# power.net
KiCad netlist of a schematic drawn in Altium Designer
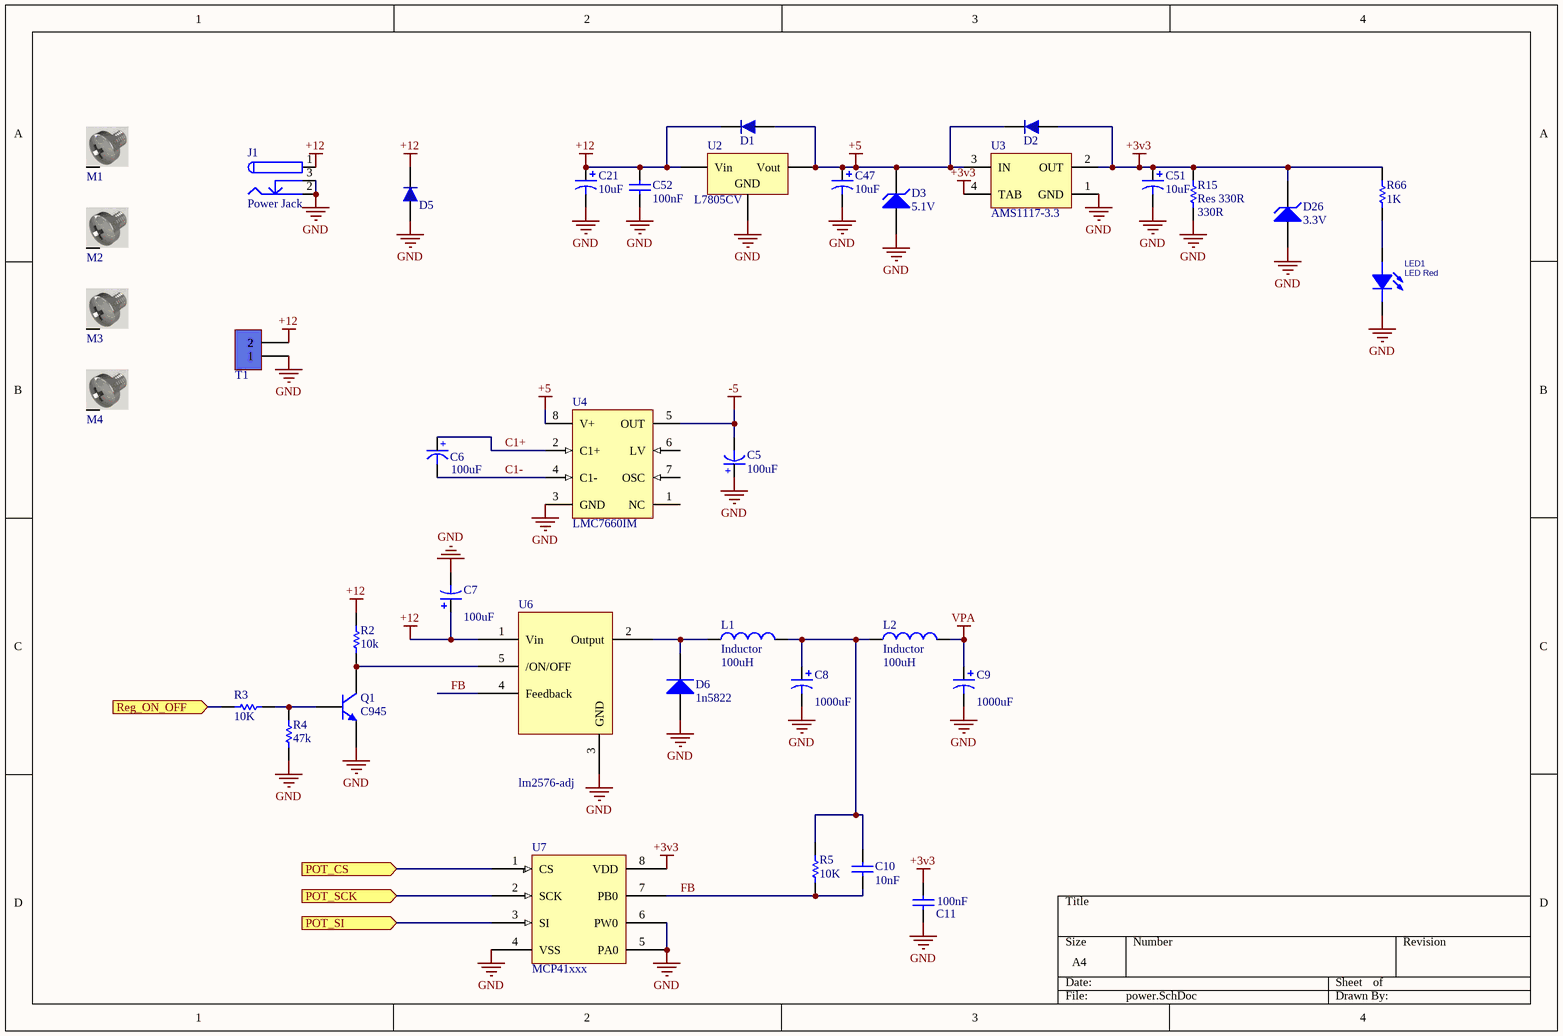
[diagram p0: power.SchDoc]

(export (version "E")
  (design (tool "Eeschema 10.0.6"))
  (components
    (comp (ref "C5")
      (value "100uF")
      (footprint "Cap SMD electrolite-6.3mm")
      (description "Polar Capacitor")
      (fields (field (name "VOLTAGE") "16V") (field (name "DESIGNER") "Saeid Jorablo"))
      (libsource (lib "Altium") (part "Cap-Polar"))
    )
    (comp (ref "C6")
      (value "100uF")
      (footprint "Cap SMD electrolite-6.3mm")
      (description "Polar Capacitor")
      (fields (field (name "VOLTAGE") "16V") (field (name "DESIGNER") "Saeid Jorablo"))
      (libsource (lib "Altium") (part "Cap-Polar"))
    )
    (comp (ref "C7")
      (value "100uF")
      (footprint "Cap SMD electrolite-6.3mm")
      (description "Polarized Capacitor (Radial)")
      (fields (field (name "PUBLISHER") "Altium Limited"))
      (libsource (lib "Miscellaneous Devices") (part "Cap Pol1"))
    )
    (comp (ref "C8")
      (value "1000uF")
      (footprint "PcbLib1:Cap SMD electrolite-10.3mm")
      (description "Polarized Capacitor (Radial)")
      (fields (field (name "PUBLISHER") "Altium Limited"))
      (libsource (lib "Miscellaneous Devices") (part "Cap Pol1"))
    )
    (comp (ref "C9")
      (value "1000uF")
      (footprint "PcbLib1:Cap SMD electrolite-10.3mm")
      (description "Polarized Capacitor (Radial)")
      (fields (field (name "PUBLISHER") "Altium Limited"))
      (libsource (lib "Miscellaneous Devices") (part "Cap Pol1"))
    )
    (comp (ref "C10")
      (value "10nF")
      (footprint "SMD_CAP_0805")
      (description "CAP-100Nf")
      (libsource (lib "Altium library (www.AVRelec.com)") (part "Cap ceramic"))
    )
    (comp (ref "C11")
      (value "100nF")
      (footprint "SMD_CAP_0805")
      (description "CAP-100Nf")
      (libsource (lib "Altium library (www.AVRelec.com)") (part "Cap ceramic"))
    )
    (comp (ref "C21")
      (value "10uF")
      (footprint "CAP0805")
      (description "CAP seramic")
      (fields (field (name "Comment") "cap 10uF") (field (name "PUBLISHER") "Altium Limited"))
      (libsource (lib "Miscellaneous Devices") (part "Cap Pol1"))
    )
    (comp (ref "C47")
      (value "10uF")
      (footprint "CAP0805")
      (description "CAP seramic")
      (fields (field (name "Comment") "cap 10uF") (field (name "PUBLISHER") "Altium Limited"))
      (libsource (lib "Miscellaneous Devices") (part "Cap Pol1"))
    )
    (comp (ref "C51")
      (value "10uF")
      (footprint "CAP0805")
      (description "CAP seramic")
      (fields (field (name "Comment") "cap 10uF") (field (name "PUBLISHER") "Altium Limited"))
      (libsource (lib "Miscellaneous Devices") (part "Cap Pol1"))
    )
    (comp (ref "C52")
      (value "100nF")
      (footprint "CAP0805")
      (description "CAP seramic")
      (fields (field (name "Comment") "cap 100nF"))
      (libsource (lib "Altium library (www.AVRelec.com)") (part "Cap ceramic"))
    )
    (comp (ref "D1")
      (value "uf4007")
      (footprint "DIOM4629X24N")
      (description "Standard Rectifiers")
      (fields (field (name "MANUFACTURER") "DC COMPONENTS") (field (name "DESIGNER") "Abbas Basereh"))
      (libsource (lib "Altium (2)") (part "1n4007 SMD M7"))
    )
    (comp (ref "D2")
      (value "uf4007")
      (footprint "DIOM4629X24N")
      (description "Standard Rectifiers")
      (fields (field (name "MANUFACTURER") "DC COMPONENTS") (field (name "DESIGNER") "Abbas Basereh"))
      (libsource (lib "Altium (2)") (part "1n4007 SMD M7"))
    )
    (comp (ref "D3")
      (value "5.1V")
      (footprint "Diode 1n4148 SMD")
      (description "Zener Diode")
      (fields (field (name "PUBLISHER") "Altium Limited"))
      (libsource (lib "Miscellaneous Devices") (part "D Zener"))
    )
    (comp (ref "D5")
      (value "uf4007")
      (footprint "DIOM4629X24N")
      (description "Standard Rectifiers")
      (fields (field (name "MANUFACTURER") "DC COMPONENTS") (field (name "DESIGNER") "Abbas Basereh"))
      (libsource (lib "Altium (2)") (part "1n4007 SMD M7"))
    )
    (comp (ref "D6")
      (value "1n5822")
      (footprint "DO214AC SMA")
      (description "1 Amp General Purpose Rectifier")
      (fields (field (name "PUBLISHER") "Altium Limited"))
      (libsource (lib "Miscellaneous Devices") (part "Diode 1N4007"))
    )
    (comp (ref "D26")
      (value "3.3V")
      (footprint "Diode 1n4148 SMD")
      (description "Zener Diode")
      (fields (field (name "PUBLISHER") "Altium Limited"))
      (libsource (lib "Miscellaneous Devices") (part "D Zener"))
    )
    (comp (ref "J1")
      (value "Power Jack")
      (footprint "Power Jack")
      (fields (field (name "DESIGNER") "Saeid Jorablo"))
      (libsource (lib "My Library") (part "Power Jack"))
    )
    (comp (ref "L1")
      (value "Inductor")
      (footprint "inductor")
      (description "SMD Inductor")
      (fields (field (name "ALTIUM_VALUE") "100uH") (field (name "PUBLISHER") "Altium Limited"))
      (libsource (lib "Miscellaneous Devices") (part "Inductor"))
    )
    (comp (ref "L2")
      (value "Inductor")
      (footprint "inductor")
      (fields (field (name "ALTIUM_VALUE") "100uH") (field (name "PUBLISHER") "Altium Limited"))
      (libsource (lib "Miscellaneous Devices") (part "Inductor"))
    )
    (comp (ref "LED1")
      (value "LED Red")
      (footprint "led_0805")
      (description "Light Emitting Diode")
      (fields (field (name "DESIGNER") "Abbas Basereh"))
      (libsource (lib "Altium (2)") (part "LED 5MM"))
    )
    (comp (ref "M1")
      (value "Screw")
      (footprint "Screw")
      (description "Board Screw With Spacer")
      (libsource (lib "My Library") (part "Board Screw"))
    )
    (comp (ref "M2")
      (value "Screw")
      (footprint "Screw")
      (description "Board Screw With Spacer")
      (libsource (lib "My Library") (part "Board Screw"))
    )
    (comp (ref "M3")
      (value "Screw")
      (footprint "Screw")
      (description "Board Screw With Spacer")
      (libsource (lib "My Library") (part "Board Screw"))
    )
    (comp (ref "M4")
      (value "Screw")
      (footprint "Screw")
      (description "Board Screw With Spacer")
      (libsource (lib "My Library") (part "Board Screw"))
    )
    (comp (ref "Q1")
      (value "C945")
      (footprint "SOT23_N")
      (description "NPN Silicon Epitaxial Planar Transistor")
      (fields (field (name "PUBLISHER") "Abbas Basereh"))
      (libsource (lib "Altium (2)") (part "C945"))
    )
    (comp (ref "R2")
      (value "10k")
      (footprint "RES 0805 (2012X06L)")
      (description "Resistor")
      (fields (field (name "PUBLISHER") "Altium Limited"))
      (libsource (lib "Miscellaneous Devices") (part "Res1"))
    )
    (comp (ref "R3")
      (value "10K")
      (footprint "RES 0805 (2012X06L)")
      (description "Resistor")
      (fields (field (name "PUBLISHER") "Altium Limited"))
      (libsource (lib "Miscellaneous Devices") (part "Res1"))
    )
    (comp (ref "R4")
      (value "47k")
      (footprint "RES 0805 (2012X06L)")
      (description "Resistor")
      (fields (field (name "PUBLISHER") "Altium Limited"))
      (libsource (lib "Miscellaneous Devices") (part "Res1"))
    )
    (comp (ref "R5")
      (value "10K")
      (footprint "RES 0805 (2012X06L)")
      (description "RES Axial 0.25W")
      (fields (field (name "DESIGNER") "Abbas Basereh"))
      (libsource (lib "Altium (2)") (part "RES Axial 0.25W"))
    )
    (comp (ref "R15")
      (value "Res 330R")
      (footprint "RES0805")
      (description "Resistor")
      (fields (field (name "ALTIUM_VALUE") "330R") (field (name "PUBLISHER") "Altium Limited"))
      (libsource (lib "Miscellaneous Devices") (part "Res1"))
    )
    (comp (ref "R66")
      (value "1K")
      (footprint "RES 0805 (2012X06L)")
      (description "RES Axial 0.25W")
      (fields (field (name "DESIGNER") "Abbas Basereh"))
      (libsource (lib "Altium (2)") (part "RES Axial 0.25W"))
    )
    (comp (ref "T1")
      (value "Terminal")
      (footprint "Terminal 1*2_1")
      (description "Terminal 2 Pin 250VAC 16A")
      (fields (field (name "DESIGNER") "Seyed Mohsen Ghasemain") (field (name "E-MAIL") "picpars@gmail.com"))
      (libsource (lib "PicPars.com_usefully_Library") (part "Terminal 1*2"))
    )
    (comp (ref "U2")
      (value "L7805CV")
      (footprint "REG-7805-smd")
      (description "Linear Voltage Regulator IC Positive FIXED")
      (fields (field (name "MANUFACTURER") "STMicroelectronics") (field (name "DESIGNER") "Abbas Basereh"))
      (libsource (lib "Altium (2)") (part "L7805CV-Linear Voltage Regulator IC Positive 1 Output 5V 1.5A TO-220AB"))
    )
    (comp (ref "U3")
      (value "AMS1117-3.3")
      (footprint "SOT223")
      (description "x.x Volt, 800mA Low-Dropout Linear Regulator, 4-pin SOT-223")
      (fields (field (name "DESIGNER") "Ali Hafizi"))
      (libsource (lib "Altium (2)") (part "AMS1117-x.x"))
    )
    (comp (ref "U4")
      (value "LMC7660IM")
      (footprint "M08A_N")
      (description "Switched Capacitor Voltage Converter")
      (fields
        (field (name "MANUFACTURER") "National Semiconductor")
        (field (name "DIGIKEYPARTNUMBER") "LMC7660IM-ND")
        (field (name "PUBLISHER") "Altium Limited")
      )
      (libsource (lib "NSC Switch Caps") (part "LMC7660IM"))
    )
    (comp (ref "U6") (value "lm2576-adj") (footprint "2596") (libsource (lib "No.2") (part "lm2596")))
    (comp (ref "U7") (value "MCP41xxx") (footprint "SO8_M") (libsource (lib "PA_sch") (part "MCP41xxx")))
  )
  (nets
    (net (code "1") (name "+3v3") (class "Default")
      (node (ref "C11") (pin "2") (pinfunction "2_2") (pintype "passive"))
      (node (ref "C51") (pin "1") (pinfunction "1_1") (pintype "passive"))
      (node (ref "D2") (pin "1") (pintype "passive"))
      (node (ref "D26") (pin "2") (pinfunction "K_2") (pintype "passive"))
      (node (ref "R15") (pin "2") (pinfunction "2_2") (pintype "passive"))
      (node (ref "R66") (pin "2") (pinfunction "2_2") (pintype "passive"))
      (node (ref "U3") (pin "2") (pinfunction "OUT_2") (pintype "power_in"))
      (node (ref "U3") (pin "4") (pinfunction "TAB_4") (pintype "power_in"))
      (node (ref "U7") (pin "8") (pinfunction "VDD_8") (pintype "power_in"))
    )
    (net (code "2") (name "+5") (class "Default")
      (node (ref "C47") (pin "1") (pinfunction "1_1") (pintype "passive"))
      (node (ref "D1") (pin "1") (pintype "passive"))
      (node (ref "D2") (pin "2") (pintype "passive"))
      (node (ref "D3") (pin "2") (pinfunction "K_2") (pintype "passive"))
      (node (ref "U2") (pin "3") (pinfunction "Vout_3") (pintype "passive"))
      (node (ref "U3") (pin "3") (pinfunction "IN_3") (pintype "power_in"))
      (node (ref "U4") (pin "8") (pinfunction "V+_8") (pintype "power_in"))
    )
    (net (code "3") (name "+12") (class "Default")
      (node (ref "C21") (pin "1") (pinfunction "1_1") (pintype "passive"))
      (node (ref "C52") (pin "1") (pinfunction "1_1") (pintype "passive"))
      (node (ref "C7") (pin "1") (pinfunction "1_1") (pintype "passive"))
      (node (ref "D1") (pin "2") (pintype "passive"))
      (node (ref "D5") (pin "2") (pintype "passive"))
      (node (ref "J1") (pin "1") (pinfunction "1_1") (pintype "power_in"))
      (node (ref "R2") (pin "2") (pinfunction "2_2") (pintype "passive"))
      (node (ref "T1") (pin "2") (pinfunction "2_2") (pintype "passive"))
      (node (ref "U2") (pin "1") (pinfunction "Vin_1") (pintype "passive"))
      (node (ref "U6") (pin "1") (pinfunction "Vin_1") (pintype "power_in"))
    )
    (net (code "4") (name "-5") (class "Default")
      (node (ref "C5") (pin "2") (pinfunction "-_2") (pintype "passive"))
      (node (ref "U4") (pin "5") (pinfunction "OUT_5") (pintype "power_in"))
    )
    (net (code "5") (name "/C1+") (class "Default")
      (node (ref "C6") (pin "1") (pinfunction "+_1") (pintype "passive"))
      (node (ref "U4") (pin "2") (pinfunction "C1+_2") (pintype "input"))
    )
    (net (code "6") (name "/C1-") (class "Default")
      (node (ref "C6") (pin "2") (pinfunction "-_2") (pintype "passive"))
      (node (ref "U4") (pin "4") (pinfunction "C1-_4") (pintype "input"))
    )
    (net (code "7") (name "/FB") (class "Default")
      (node (ref "C10") (pin "2") (pinfunction "2_2") (pintype "passive"))
      (node (ref "R5") (pin "1") (pinfunction "1_1") (pintype "passive"))
      (node (ref "U6") (pin "4") (pinfunction "Feedback_4") (pintype "power_in"))
      (node (ref "U7") (pin "7") (pinfunction "PB0_7") (pintype "passive"))
    )
    (net (code "8") (name "/POT_CS") (class "Default")
      (node (ref "U7") (pin "1") (pinfunction "CS_1") (pintype "input"))
    )
    (net (code "9") (name "/POT_SCK") (class "Default")
      (node (ref "U7") (pin "2") (pinfunction "SCK_2") (pintype "input"))
    )
    (net (code "10") (name "/POT_SI") (class "Default")
      (node (ref "U7") (pin "3") (pinfunction "SI_3") (pintype "input"))
    )
    (net (code "11") (name "/Reg_ON_OFF") (class "Default")
      (node (ref "R3") (pin "1") (pinfunction "1_1") (pintype "passive"))
    )
    (net (code "12") (name "GND") (class "Default")
      (node (ref "C11") (pin "1") (pinfunction "1_1") (pintype "passive"))
      (node (ref "C21") (pin "2") (pinfunction "2_2") (pintype "passive"))
      (node (ref "C47") (pin "2") (pinfunction "2_2") (pintype "passive"))
      (node (ref "C5") (pin "1") (pinfunction "+_1") (pintype "passive"))
      (node (ref "C51") (pin "2") (pinfunction "2_2") (pintype "passive"))
      (node (ref "C52") (pin "2") (pinfunction "2_2") (pintype "passive"))
      (node (ref "C7") (pin "2") (pinfunction "2_2") (pintype "passive"))
      (node (ref "C8") (pin "2") (pinfunction "2_2") (pintype "passive"))
      (node (ref "C9") (pin "2") (pinfunction "2_2") (pintype "passive"))
      (node (ref "D26") (pin "1") (pinfunction "A_1") (pintype "passive"))
      (node (ref "D3") (pin "1") (pinfunction "A_1") (pintype "passive"))
      (node (ref "D5") (pin "1") (pintype "passive"))
      (node (ref "D6") (pin "1") (pinfunction "A_1") (pintype "passive"))
      (node (ref "J1") (pin "2") (pinfunction "2_2") (pintype "power_in"))
      (node (ref "J1") (pin "3") (pinfunction "3_3") (pintype "power_in"))
      (node (ref "LED1") (pin "2") (pinfunction "CATHODE_2") (pintype "passive"))
      (node (ref "Q1") (pin "2") (pinfunction "E_2") (pintype "passive"))
      (node (ref "R15") (pin "1") (pinfunction "1_1") (pintype "passive"))
      (node (ref "R4") (pin "1") (pinfunction "1_1") (pintype "passive"))
      (node (ref "T1") (pin "1") (pinfunction "1_1") (pintype "passive"))
      (node (ref "U2") (pin "2") (pinfunction "GND_2") (pintype "passive"))
      (node (ref "U3") (pin "1") (pinfunction "GND_1") (pintype "power_in"))
      (node (ref "U4") (pin "3") (pinfunction "GND_3") (pintype "power_in"))
      (node (ref "U6") (pin "3") (pinfunction "GND_3") (pintype "power_in"))
      (node (ref "U7") (pin "4") (pinfunction "VSS_4") (pintype "power_in"))
      (node (ref "U7") (pin "5") (pinfunction "PA0_5") (pintype "passive"))
      (node (ref "U7") (pin "6") (pinfunction "PW0_6") (pintype "passive"))
    )
    (net (code "13") (name "Net-(C10-Pad1)") (class "Default")
      (node (ref "C10") (pin "1") (pinfunction "1_1") (pintype "passive"))
      (node (ref "C8") (pin "1") (pinfunction "1_1") (pintype "passive"))
      (node (ref "L1") (pin "2") (pinfunction "2_2") (pintype "passive"))
      (node (ref "L2") (pin "1") (pinfunction "1_1") (pintype "passive"))
      (node (ref "R5") (pin "2") (pinfunction "2_2") (pintype "passive"))
    )
    (net (code "14") (name "Net-(D6-K)") (class "Default")
      (node (ref "D6") (pin "2") (pinfunction "K_2") (pintype "passive"))
      (node (ref "L1") (pin "1") (pinfunction "1_1") (pintype "passive"))
      (node (ref "U6") (pin "2") (pinfunction "Output_2") (pintype "power_in"))
    )
    (net (code "15") (name "Net-(LED1-ANODE)") (class "Default")
      (node (ref "LED1") (pin "1") (pinfunction "ANODE_1") (pintype "passive"))
      (node (ref "R66") (pin "1") (pinfunction "1_1") (pintype "passive"))
    )
    (net (code "16") (name "Net-(Q1-B)") (class "Default")
      (node (ref "Q1") (pin "1") (pinfunction "B_1") (pintype "passive"))
      (node (ref "R3") (pin "2") (pinfunction "2_2") (pintype "passive"))
      (node (ref "R4") (pin "2") (pinfunction "2_2") (pintype "passive"))
    )
    (net (code "17") (name "Net-(Q1-C)") (class "Default")
      (node (ref "Q1") (pin "3") (pinfunction "C_3") (pintype "passive"))
      (node (ref "R2") (pin "1") (pinfunction "1_1") (pintype "passive"))
      (node (ref "U6") (pin "5") (pinfunction "/ON/OFF_5") (pintype "power_in"))
    )
    (net (code "18") (name "VPA") (class "Default")
      (node (ref "C9") (pin "1") (pinfunction "1_1") (pintype "passive"))
      (node (ref "L2") (pin "2") (pinfunction "2_2") (pintype "passive"))
    )
    (net (code "19") (name "unconnected-(M1-PadS)") (class "Default")
      (node (ref "M1") (pin "S") (pinfunction "S_S") (pintype "passive"))
    )
    (net (code "20") (name "unconnected-(M2-PadS)") (class "Default")
      (node (ref "M2") (pin "S") (pinfunction "S_S") (pintype "passive"))
    )
    (net (code "21") (name "unconnected-(M3-PadS)") (class "Default")
      (node (ref "M3") (pin "S") (pinfunction "S_S") (pintype "passive"))
    )
    (net (code "22") (name "unconnected-(M4-PadS)") (class "Default")
      (node (ref "M4") (pin "S") (pinfunction "S_S") (pintype "passive"))
    )
    (net (code "23") (name "unconnected-(U4-LV-Pad6)") (class "Default")
      (node (ref "U4") (pin "6") (pinfunction "LV_6") (pintype "input"))
    )
    (net (code "24") (name "unconnected-(U4-NC-Pad1)") (class "Default")
      (node (ref "U4") (pin "1") (pinfunction "NC_1") (pintype "passive"))
    )
    (net (code "25") (name "unconnected-(U4-OSC-Pad7)") (class "Default")
      (node (ref "U4") (pin "7") (pinfunction "OSC_7") (pintype "input"))
    )
  )
)
